# DM1092_IMX378.net
KiCad netlist of a schematic drawn in Altium Designer
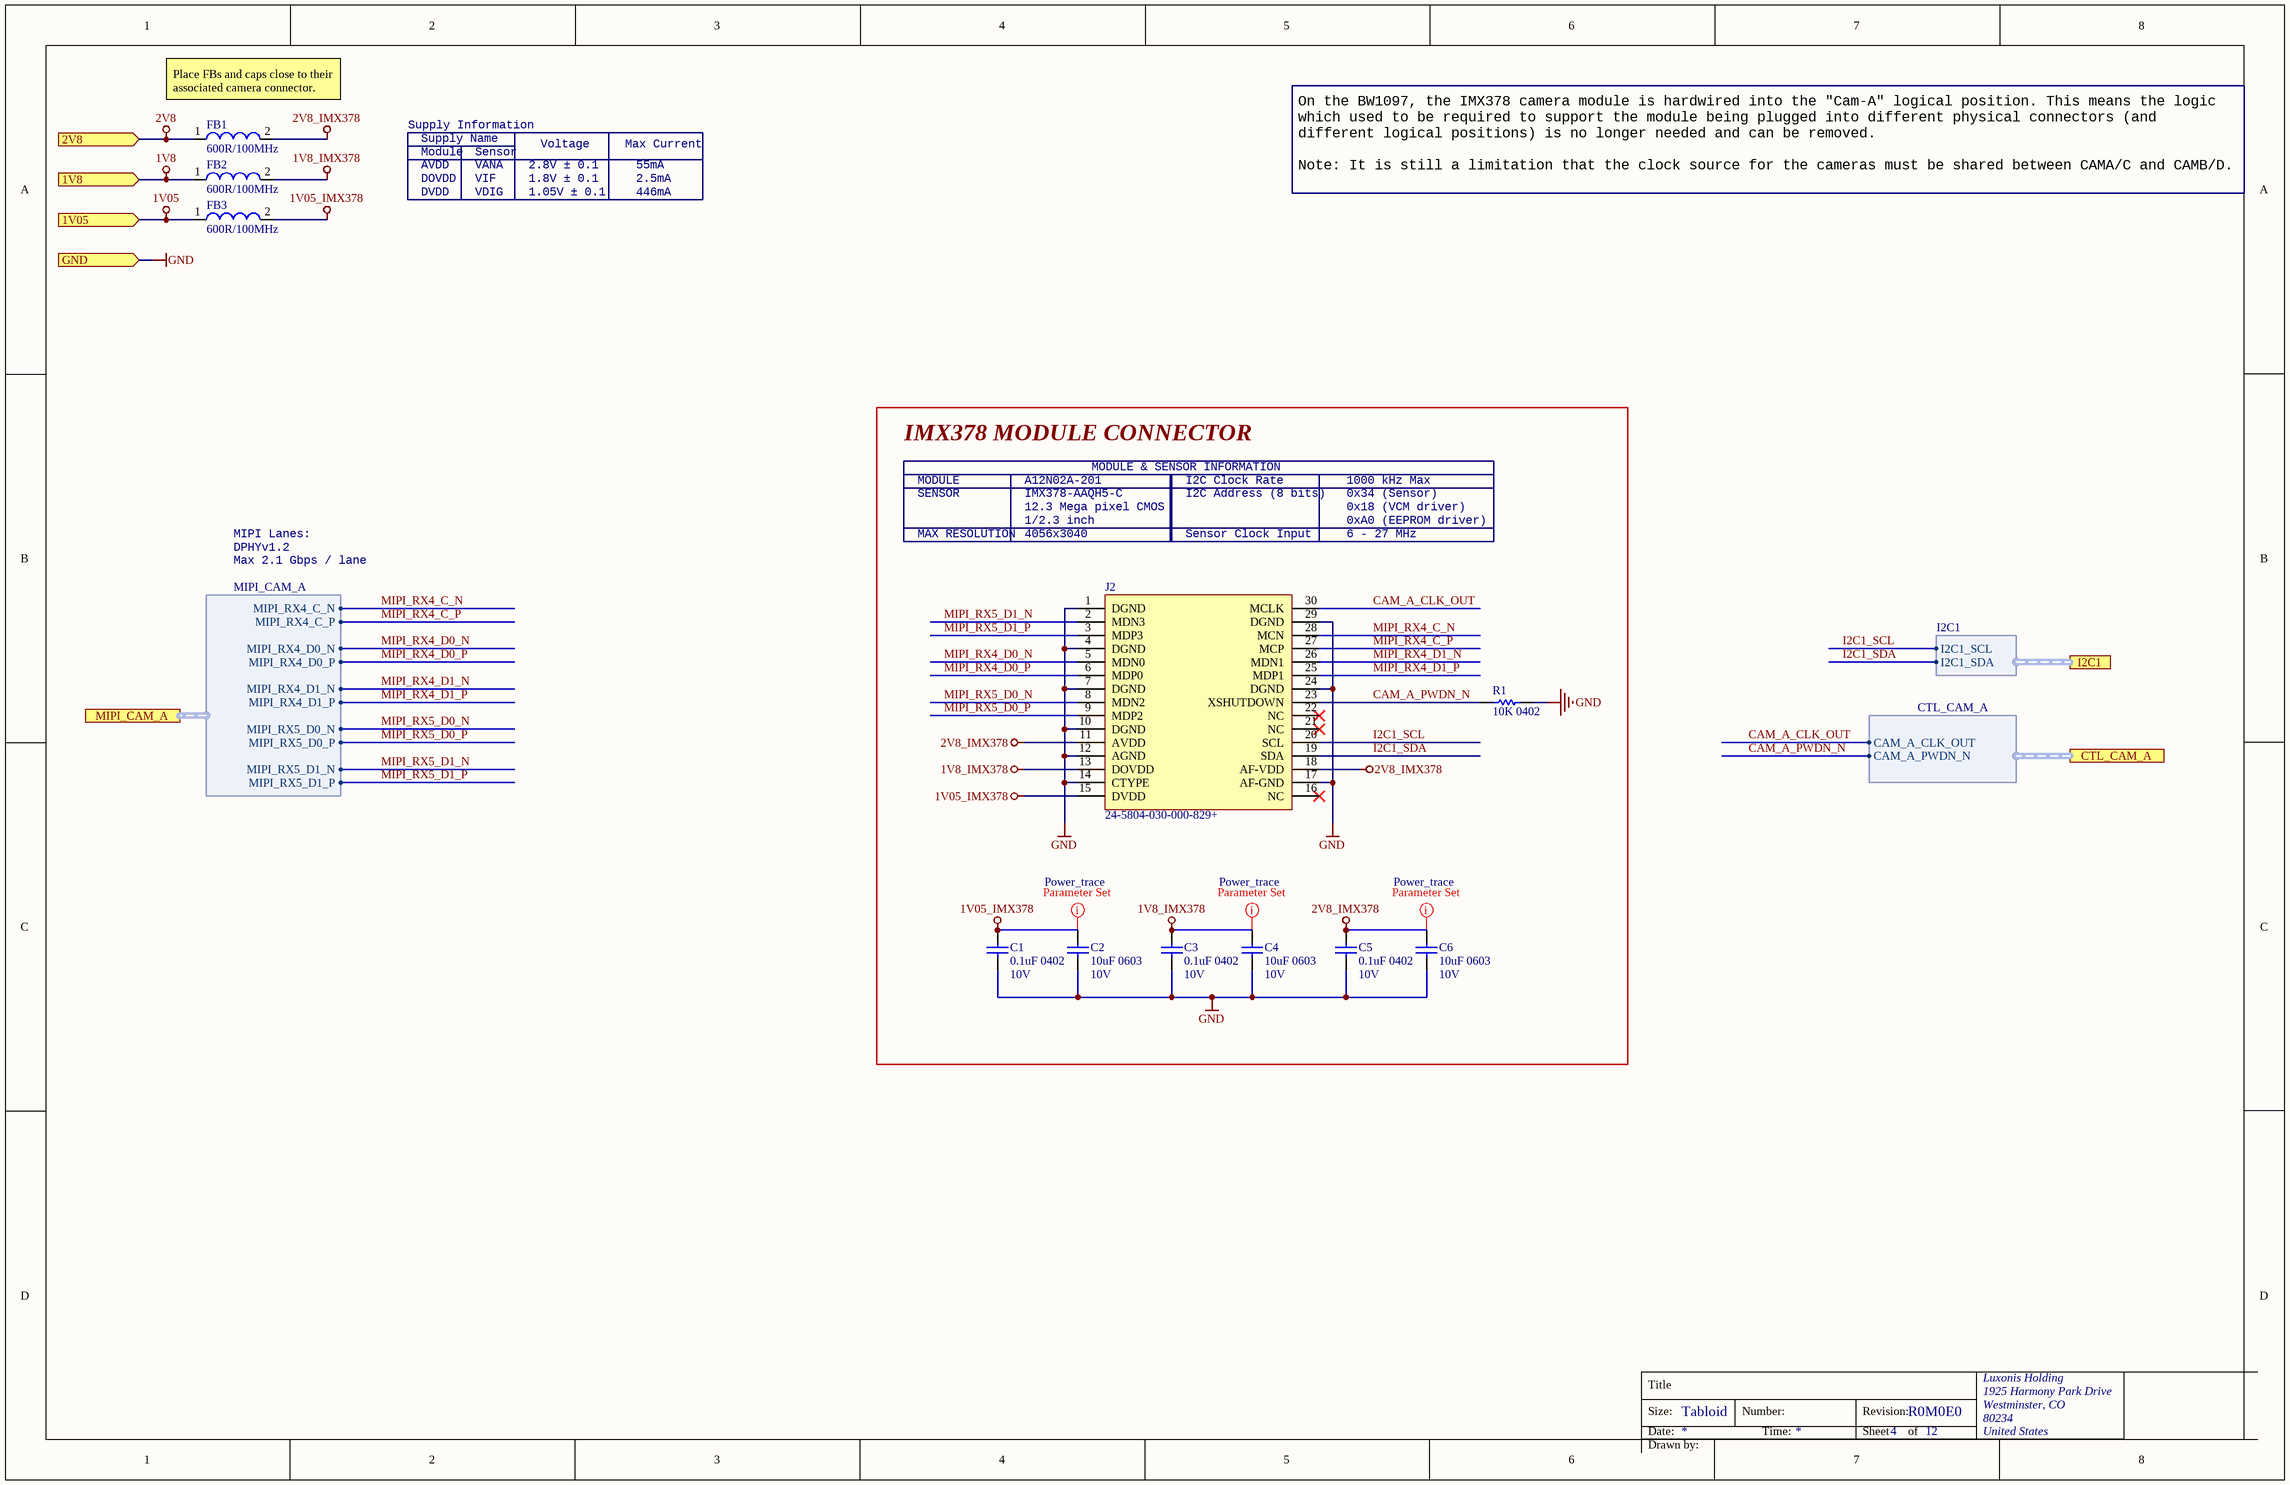
[diagram p0: DM1092_IMX378.SchDoc]

(export (version "E")
  (design (tool "Eeschema 10.0.6"))
  (components
    (comp (ref "C1")
      (value "0.1uF 0402")
      (footprint "CAP_Altium_Vault_Generic:CAPC0402(1005)70_L")
      (description "CAP CER 0.1UF 10V X7R 0402 5%")
      (fields (field (name "TOLERANCE") "5%") (field (name "VOLTAGE RATING") "10V"))
      (libsource (lib "LuxonisMaster") (part "GRM155R71A104JA01D"))
    )
    (comp (ref "C2")
      (value "10uF 0603")
      (footprint "CAP_Altium_Vault_Generic:CAPC0603(1608)100_L")
      (description "CAP CER 10UF 10V X5R 0603 20%")
      (fields (field (name "TOLERANCE") "20%") (field (name "VOLTAGE RATING") "10V"))
      (libsource (lib "LuxonisMaster") (part "GRM188R61A106ME69D"))
    )
    (comp (ref "C3")
      (value "0.1uF 0402")
      (footprint "CAP_Altium_Vault_Generic:CAPC0402(1005)70_L")
      (description "CAP CER 0.1UF 10V X7R 0402 5%")
      (fields (field (name "TOLERANCE") "5%") (field (name "VOLTAGE RATING") "10V"))
      (libsource (lib "LuxonisMaster") (part "GRM155R71A104JA01D"))
    )
    (comp (ref "C4")
      (value "10uF 0603")
      (footprint "CAP_Altium_Vault_Generic:CAPC0603(1608)100_L")
      (description "CAP CER 10UF 10V X5R 0603 20%")
      (fields (field (name "TOLERANCE") "20%") (field (name "VOLTAGE RATING") "10V"))
      (libsource (lib "LuxonisMaster") (part "GRM188R61A106ME69D"))
    )
    (comp (ref "C5")
      (value "0.1uF 0402")
      (footprint "CAP_Altium_Vault_Generic:CAPC0402(1005)70_L")
      (description "CAP CER 0.1UF 10V X7R 0402 5%")
      (fields (field (name "TOLERANCE") "5%") (field (name "VOLTAGE RATING") "10V"))
      (libsource (lib "LuxonisMaster") (part "GRM155R71A104JA01D"))
    )
    (comp (ref "C6")
      (value "10uF 0603")
      (footprint "CAP_Altium_Vault_Generic:CAPC0603(1608)100_L")
      (description "CAP CER 10UF 10V X5R 0603 20%")
      (fields (field (name "TOLERANCE") "20%") (field (name "VOLTAGE RATING") "10V"))
      (libsource (lib "LuxonisMaster") (part "GRM188R61A106ME69D"))
    )
    (comp (ref "FB1")
      (value "600R/100MHz")
      (footprint "LuxonisMaster:2508056017Y2")
      (description "FERRITE BEAD, 0.1OHM, 2A, 0805, 600R/100MHz")
      (fields (field (name "TOLERANCE") "25%"))
      (libsource (lib "LuxonisMaster") (part "2508056017Y2"))
    )
    (comp (ref "FB2")
      (value "600R/100MHz")
      (footprint "LuxonisMaster:2508056017Y2")
      (description "FERRITE BEAD, 0.1OHM, 2A, 0805, 600R/100MHz")
      (fields (field (name "TOLERANCE") "25%"))
      (libsource (lib "LuxonisMaster") (part "2508056017Y2"))
    )
    (comp (ref "FB3")
      (value "600R/100MHz")
      (footprint "LuxonisMaster:2508056017Y2")
      (description "FERRITE BEAD, 0.1OHM, 2A, 0805, 600R/100MHz")
      (fields (field (name "TOLERANCE") "25%"))
      (libsource (lib "LuxonisMaster") (part "2508056017Y2"))
    )
    (comp (ref "J2")
      (value "24-5804-030-000-829+")
      (footprint "LuxonisMaster:A12N02A-201_1.6mmbrd_MatedModule")
      (description "CONN Series 5804 board to board 0.4mm pitch 30 way connector")
      (libsource (lib "LuxonisMaster") (part "A12N02A-201_Connector"))
    )
    (comp (ref "R1")
      (value "10K 0402")
      (footprint "RES_Altium_Vault_Generic:RESC0402(1005)_L")
      (fields (field (name "TOLERANCE") "1%"))
      (libsource (lib "LuxonisMaster") (part "RC0402FR-1310KL"))
    )
  )
  (nets
    (net (code "4") (name "/CAM_A_CLK_OUT") (class "Default")
      (node (ref "J2") (pin "30") (pinfunction "MCLK_30") (pintype "passive"))
    )
    (net (code "5") (name "/CAM_A_PWDN_N") (class "Default")
      (node (ref "J2") (pin "23") (pinfunction "XSHUTDOWN_23") (pintype "passive"))
      (node (ref "R1") (pin "1") (pinfunction "1_1") (pintype "passive"))
    )
    (net (code "6") (name "/I2C1_SCL") (class "Default")
      (node (ref "J2") (pin "20") (pinfunction "SCL_20") (pintype "passive"))
    )
    (net (code "7") (name "/I2C1_SDA") (class "Default")
      (node (ref "J2") (pin "19") (pinfunction "SDA_19") (pintype "passive"))
    )
    (net (code "8") (name "/MIPI_RX4_C_N") (class "Default")
      (node (ref "J2") (pin "28") (pinfunction "MCN_28") (pintype "passive"))
    )
    (net (code "9") (name "/MIPI_RX4_C_P") (class "Default")
      (node (ref "J2") (pin "27") (pinfunction "MCP_27") (pintype "passive"))
    )
    (net (code "10") (name "/MIPI_RX4_D0_N") (class "Default")
      (node (ref "J2") (pin "5") (pinfunction "MDN0_5") (pintype "passive"))
    )
    (net (code "11") (name "/MIPI_RX4_D0_P") (class "Default")
      (node (ref "J2") (pin "6") (pinfunction "MDP0_6") (pintype "passive"))
    )
    (net (code "12") (name "/MIPI_RX4_D1_N") (class "Default")
      (node (ref "J2") (pin "26") (pinfunction "MDN1_26") (pintype "passive"))
    )
    (net (code "13") (name "/MIPI_RX4_D1_P") (class "Default")
      (node (ref "J2") (pin "25") (pinfunction "MDP1_25") (pintype "passive"))
    )
    (net (code "14") (name "/MIPI_RX5_D0_N") (class "Default")
      (node (ref "J2") (pin "8") (pinfunction "MDN2_8") (pintype "passive"))
    )
    (net (code "15") (name "/MIPI_RX5_D0_P") (class "Default")
      (node (ref "J2") (pin "9") (pinfunction "MDP2_9") (pintype "passive"))
    )
    (net (code "16") (name "/MIPI_RX5_D1_N") (class "Default")
      (node (ref "J2") (pin "2") (pinfunction "MDN3_2") (pintype "passive"))
    )
    (net (code "17") (name "/MIPI_RX5_D1_P") (class "Default")
      (node (ref "J2") (pin "3") (pinfunction "MDP3_3") (pintype "passive"))
    )
    (net (code "21") (name "1V05") (class "Default")
      (node (ref "FB3") (pin "1") (pinfunction "1_1") (pintype "passive"))
    )
    (net (code "22") (name "1V05_IMX378") (class "Default")
      (node (ref "C1") (pin "2") (pinfunction "2_2") (pintype "passive"))
      (node (ref "C2") (pin "2") (pinfunction "2_2") (pintype "passive"))
      (node (ref "FB3") (pin "2") (pinfunction "2_2") (pintype "passive"))
      (node (ref "J2") (pin "15") (pinfunction "DVDD_15") (pintype "passive"))
    )
    (net (code "23") (name "1V8") (class "Default")
      (node (ref "FB2") (pin "1") (pinfunction "1_1") (pintype "passive"))
    )
    (net (code "24") (name "1V8_IMX378") (class "Default")
      (node (ref "C3") (pin "2") (pinfunction "2_2") (pintype "passive"))
      (node (ref "C4") (pin "2") (pinfunction "2_2") (pintype "passive"))
      (node (ref "FB2") (pin "2") (pinfunction "2_2") (pintype "passive"))
      (node (ref "J2") (pin "13") (pinfunction "DOVDD_13") (pintype "passive"))
    )
    (net (code "25") (name "2V8") (class "Default")
      (node (ref "FB1") (pin "1") (pinfunction "1_1") (pintype "passive"))
    )
    (net (code "26") (name "2V8_IMX378") (class "Default")
      (node (ref "C5") (pin "2") (pinfunction "2_2") (pintype "passive"))
      (node (ref "C6") (pin "2") (pinfunction "2_2") (pintype "passive"))
      (node (ref "FB1") (pin "2") (pinfunction "2_2") (pintype "passive"))
      (node (ref "J2") (pin "11") (pinfunction "AVDD_11") (pintype "passive"))
      (node (ref "J2") (pin "18") (pinfunction "AF-VDD_18") (pintype "passive"))
    )
    (net (code "27") (name "GND") (class "Default")
      (node (ref "C1") (pin "1") (pinfunction "1_1") (pintype "passive"))
      (node (ref "C2") (pin "1") (pinfunction "1_1") (pintype "passive"))
      (node (ref "C3") (pin "1") (pinfunction "1_1") (pintype "passive"))
      (node (ref "C4") (pin "1") (pinfunction "1_1") (pintype "passive"))
      (node (ref "C5") (pin "1") (pinfunction "1_1") (pintype "passive"))
      (node (ref "C6") (pin "1") (pinfunction "1_1") (pintype "passive"))
      (node (ref "J2") (pin "1") (pinfunction "DGND_1") (pintype "passive"))
      (node (ref "J2") (pin "10") (pinfunction "DGND_10") (pintype "passive"))
      (node (ref "J2") (pin "12") (pinfunction "AGND_12") (pintype "passive"))
      (node (ref "J2") (pin "14") (pinfunction "CTYPE_14") (pintype "passive"))
      (node (ref "J2") (pin "17") (pinfunction "AF-GND_17") (pintype "passive"))
      (node (ref "J2") (pin "24") (pinfunction "DGND_24") (pintype "passive"))
      (node (ref "J2") (pin "29") (pinfunction "DGND_29") (pintype "passive"))
      (node (ref "J2") (pin "4") (pinfunction "DGND_4") (pintype "passive"))
      (node (ref "J2") (pin "7") (pinfunction "DGND_7") (pintype "passive"))
      (node (ref "R1") (pin "2") (pinfunction "2_2") (pintype "passive"))
    )
    (net (code "28") (name "unconnected-(J2-NC-Pad16)") (class "Default")
      (node (ref "J2") (pin "16") (pinfunction "NC_16") (pintype "passive+no_connect"))
    )
    (net (code "29") (name "unconnected-(J2-NC-Pad21)") (class "Default")
      (node (ref "J2") (pin "21") (pinfunction "NC_21") (pintype "passive+no_connect"))
    )
    (net (code "30") (name "unconnected-(J2-NC-Pad22)") (class "Default")
      (node (ref "J2") (pin "22") (pinfunction "NC_22") (pintype "passive+no_connect"))
    )
  )
)
